# Board_power.net
KiCad netlist of a schematic drawn in Altium Designer
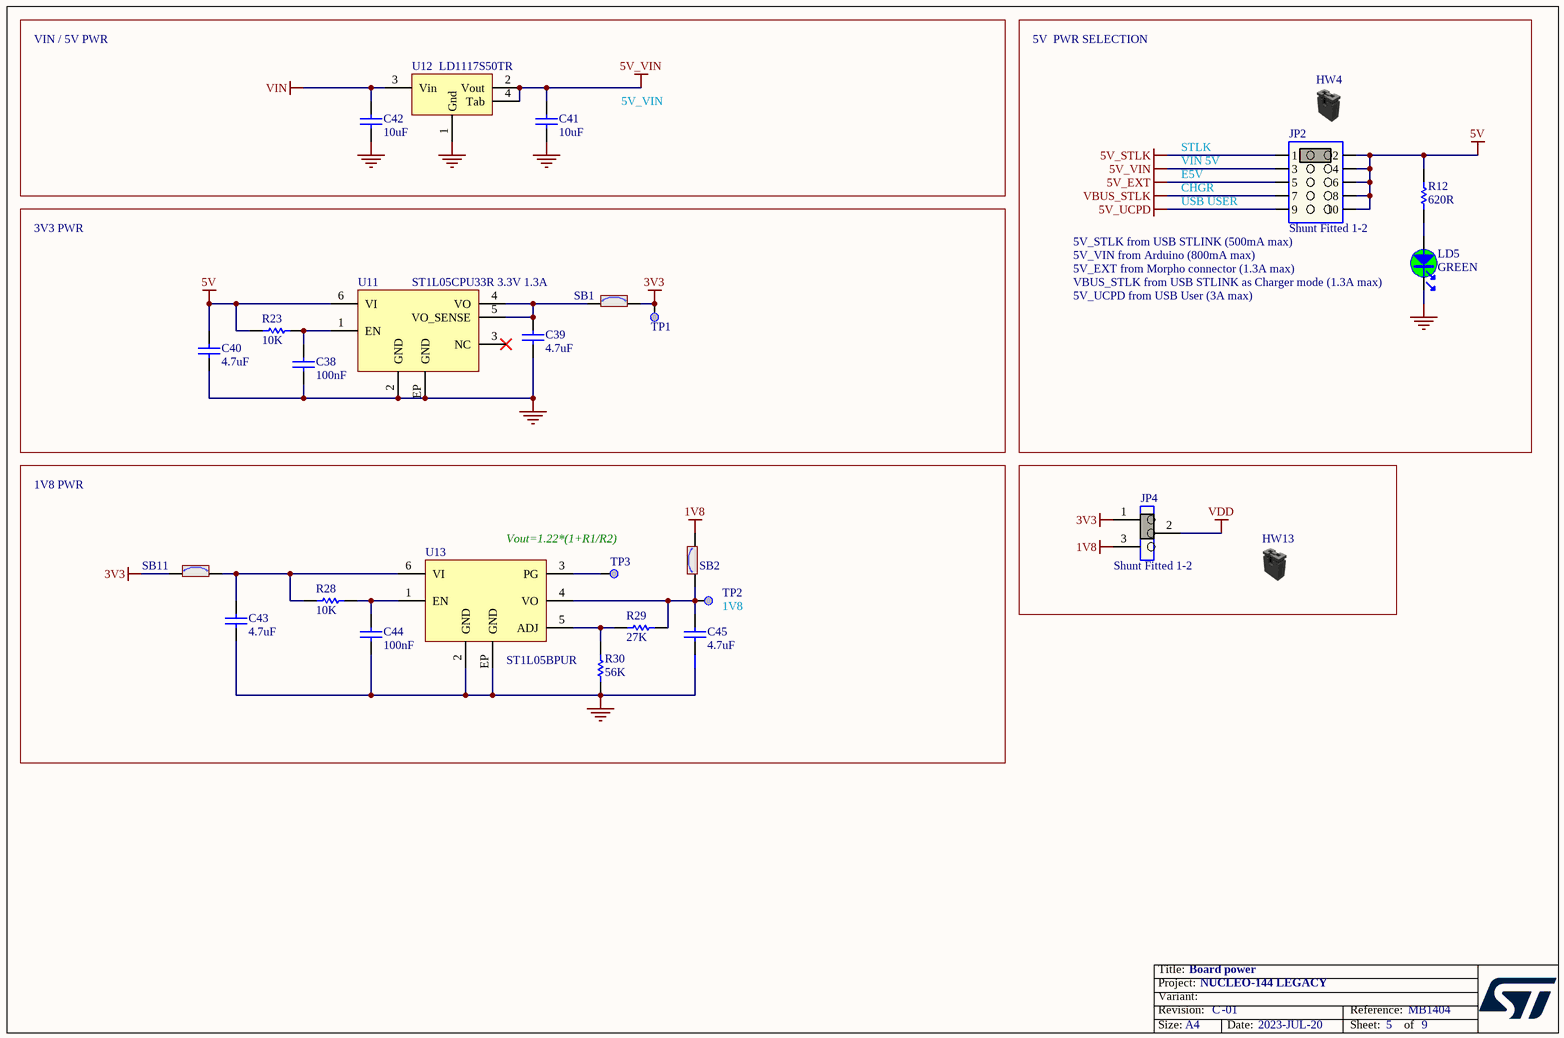
[diagram p0: Board_power.SchDoc]

(export (version "E")
  (design (tool "Eeschema 10.0.6"))
  (components
    (comp (ref "C38")
      (value "100nF")
      (footprint "MCD_PARTS:C0402")
      (description "Capacitor, MLCC, 100nF, 16V, X7R, 10%, 0402, T=0.5mm")
      (fields
        (field (name "INTERNAL_PART_NUMBER") "MCD-00006")
        (field (name "MANUFACTURER_PART_NUMBER") "CC0402KRX7R7BB104")
        (field (name "PROVIDED_BY") "SUBCO")
      )
      (libsource (lib "MCD_PARTS_database") (part "Capacitor"))
    )
    (comp (ref "C39")
      (value "4.7uF")
      (footprint "C0603_H0P8")
      (description "Capacitor, MLCC, 4.7uF, 10V, X5R, +/-20%, 0603, T=0.8mm")
      (fields (field (name "INTERNAL_PART_NUMBER") "MCD-03342") (field (name "MANUFACTURER") "YAGEO"))
      (libsource (lib "MCD_PARTS_database") (part "Capacitor"))
    )
    (comp (ref "C40")
      (value "4.7uF")
      (footprint "MCD_PARTS:C0603")
      (description "Capacitor, MLCC, 4.7uF, 16V, X5R, 20%, 0603, T=0,8mm")
      (fields
        (field (name "INTERNAL_PART_NUMBER") "MCD-00097")
        (field (name "MANUFACTURER_PART_NUMBER") "GRM188R61C475KE11")
        (field (name "PROVIDED_BY") "SUBCO")
      )
      (libsource (lib "MCD_PARTS_database") (part "Capacitor"))
    )
    (comp (ref "C41")
      (value "10uF")
      (footprint "MCD_PARTS:C0805")
      (description "Capacitor, MLCC, 10uF, 25V, X5R, 10%, 0805, T=0,85mm")
      (fields
        (field (name "INTERNAL_PART_NUMBER") "MCD-00014")
        (field (name "MANUFACTURER_PART_NUMBER") "CC0805KRX5R8BB106")
        (field (name "PROVIDED_BY") "SUBCO")
      )
      (libsource (lib "MCD_PARTS_database") (part "Capacitor"))
    )
    (comp (ref "C42")
      (value "10uF")
      (footprint "MCD_PARTS:C0805")
      (description "Capacitor, MLCC, 10uF, 25V, X5R, 10%, 0805, T=0,85mm")
      (fields
        (field (name "INTERNAL_PART_NUMBER") "MCD-00014")
        (field (name "MANUFACTURER_PART_NUMBER") "CC0805KRX5R8BB106")
        (field (name "PROVIDED_BY") "SUBCO")
      )
      (libsource (lib "MCD_PARTS_database") (part "Capacitor"))
    )
    (comp (ref "C43")
      (value "4.7uF")
      (footprint "MCD_PARTS:C0603")
      (description "Capacitor, MLCC, 4.7uF, 16V, X5R, 20%, 0603, T=0,8mm")
      (fields
        (field (name "INTERNAL_PART_NUMBER") "MCD-00097")
        (field (name "MANUFACTURER_PART_NUMBER") "GRM188R61C475KE11")
        (field (name "PROVIDED_BY") "SUBCO")
      )
      (libsource (lib "MCD_PARTS_database") (part "Capacitor"))
    )
    (comp (ref "C44")
      (value "100nF")
      (footprint "MCD_PARTS:C0402")
      (description "Capacitor, MLCC, 100nF, 16V, X7R, 10%, 0402, T=0.5mm")
      (fields
        (field (name "INTERNAL_PART_NUMBER") "MCD-00006")
        (field (name "MANUFACTURER_PART_NUMBER") "CC0402KRX7R7BB104")
        (field (name "PROVIDED_BY") "SUBCO")
      )
      (libsource (lib "MCD_PARTS_database") (part "Capacitor"))
    )
    (comp (ref "C45")
      (value "4.7uF")
      (footprint "C0603_H0P8")
      (description "Capacitor, MLCC, 4.7uF, 10V, X5R, +/-20%, 0603, T=0.8mm")
      (fields (field (name "INTERNAL_PART_NUMBER") "MCD-03342") (field (name "MANUFACTURER") "YAGEO"))
      (libsource (lib "MCD_PARTS_database") (part "Capacitor"))
    )
    (comp (ref "HW4")
      (value "Shunt Black 2.54mm")
      (description "SHUNT 2.54mm BLACK")
      (fields
        (field (name "INTERNAL_PART_NUMBER") "MCD-00043")
        (field (name "MANUFACTURER_PART_NUMBER") "SNT-100-BK-G")
        (field (name "PROVIDED_BY") "SUBCO")
      )
      (libsource (lib "MCD_PARTS_database") (part "Shunt Black 2.54mm"))
    )
    (comp (ref "HW13")
      (value "Shunt Black 2.54mm")
      (description "SHUNT 2.54mm BLACK")
      (fields
        (field (name "INTERNAL_PART_NUMBER") "MCD-00043")
        (field (name "MANUFACTURER_PART_NUMBER") "SNT-100-BK-G")
        (field (name "PROVIDED_BY") "SUBCO")
      )
      (libsource (lib "MCD_PARTS_database") (part "Shunt Black 2.54mm"))
    )
    (comp (ref "JP2")
      (value "Shunt Fitted 1-2")
      (footprint "MCD_PARTS:CON_SAMTEC_TSW-105-07-X-D")
      (description "Header, 5x2, 2,54mm, VR, TH, Height 5.84mm/2.54mm - Shunt Fitted 1-2")
      (fields (field (name "INTERNAL_PART_NUMBER") "MCD-01203") (field (name "BMS_PART_NUMBER") "9083523"))
      (libsource (lib "MCD_PARTS_database") (part "Jumper_Header 5x2 Fitted 1-2"))
    )
    (comp (ref "JP4")
      (value "Shunt Fitted 1-2")
      (footprint "MCD_PARTS:CON_SAMTEC_TSW-103-07-F-S")
      (description "Header, 3x1, 2,54mm, VR, TH, Height 5.84mm/2.54mm - Shunt Fitted 1-2 by default")
      (fields
        (field (name "INTERNAL_PART_NUMBER") "MCD-00684")
        (field (name "MANUFACTURER_PART_NUMBER") "TSW-103-07-F-S")
        (field (name "PROVIDED_BY") "SUBCO")
      )
      (libsource (lib "MCD_PARTS_database") (part "Jumper_Header 3x1 Fitted 1-2"))
    )
    (comp (ref "LD5")
      (value "GREEN")
      (footprint "MCD_PARTS:LED_0603_OSRAM_LG-Q396-PS-35_GREEN_1A2K_H0P4")
      (description "LED Green, 0603 SMD, Forward Voltage Typ=2V, Max=2.5V")
      (fields
        (field (name "INTERNAL_PART_NUMBER") "MCD-00588")
        (field (name "MANUFACTURER_PART_NUMBER") "LG Q396-PS-35")
        (field (name "PROVIDED_BY") "SUBCO")
      )
      (libsource (lib "MCD_PARTS_database") (part "LED_green"))
    )
    (comp (ref "R12")
      (value "620R")
      (footprint "MCD_PARTS:R0603")
      (description "Resistor,620R,0603,1%,1/10W")
      (fields
        (field (name "INTERNAL_PART_NUMBER") "MCD-00500")
        (field (name "MANUFACTURER_PART_NUMBER") "RC0603FR-07620RL")
        (field (name "PROVIDED_BY") "SUBCO")
      )
      (libsource (lib "MCD_PARTS_database") (part "Resistor"))
    )
    (comp (ref "R23")
      (value "10K")
      (footprint "MCD_PARTS:R0402")
      (description "Resistor,10K,0402,1%,1/16W")
      (fields
        (field (name "INTERNAL_PART_NUMBER") "MCD-00053")
        (field (name "MANUFACTURER_PART_NUMBER") "RC0402FR-0710KL")
        (field (name "PROVIDED_BY") "SUBCO")
      )
      (libsource (lib "MCD_PARTS_database") (part "Resistor"))
    )
    (comp (ref "R28")
      (value "10K")
      (footprint "MCD_PARTS:R0402")
      (description "Resistor,10K,0402,1%,1/16W")
      (fields
        (field (name "INTERNAL_PART_NUMBER") "MCD-00053")
        (field (name "MANUFACTURER_PART_NUMBER") "RC0402FR-0710KL")
        (field (name "PROVIDED_BY") "SUBCO")
      )
      (libsource (lib "MCD_PARTS_database") (part "Resistor"))
    )
    (comp (ref "R29")
      (value "27K")
      (footprint "MCD_PARTS:R0402")
      (description "Resistor,27K,0402,1%,1/16W")
      (fields
        (field (name "INTERNAL_PART_NUMBER") "MCD-00443")
        (field (name "MANUFACTURER_PART_NUMBER") "RC0402FR-0727KL")
        (field (name "PROVIDED_BY") "SUBCO")
      )
      (libsource (lib "MCD_PARTS_database") (part "Resistor"))
    )
    (comp (ref "R30")
      (value "56K")
      (footprint "MCD_PARTS:R0402")
      (description "Resistor,56K,0402,1%,1/16W")
      (fields
        (field (name "INTERNAL_PART_NUMBER") "MCD-00493")
        (field (name "MANUFACTURER_PART_NUMBER") "RC0402FR-0756KL")
        (field (name "PROVIDED_BY") "SUBCO")
      )
      (libsource (lib "MCD_PARTS_database") (part "Resistor"))
    )
    (comp (ref "SB1")
      (value "SB_ON")
      (footprint "MCD_PARTS:SOLDER-BRIDGE_R0603-0R")
      (description "Solder Bridge ON")
      (fields
        (field (name "INTERNAL_PART_NUMBER") "MCD-00071")
        (field (name "MANUFACTURER_PART_NUMBER") "RC0603JR-070RL")
        (field (name "PROVIDED_BY") "SUBCO")
      )
      (libsource (lib "MCD_PARTS_database") (part "SB_ON"))
    )
    (comp (ref "SB2")
      (value "SB_ON")
      (footprint "MCD_PARTS:SOLDER-BRIDGE_R0603-0R")
      (description "Solder Bridge ON")
      (fields
        (field (name "INTERNAL_PART_NUMBER") "MCD-00071")
        (field (name "MANUFACTURER_PART_NUMBER") "RC0603JR-070RL")
        (field (name "PROVIDED_BY") "SUBCO")
      )
      (libsource (lib "") (part "SB_ON_1"))
    )
    (comp (ref "SB11")
      (value "SB_ON")
      (footprint "MCD_PARTS:SOLDER-BRIDGE_R0603-0R")
      (description "Solder Bridge ON")
      (fields
        (field (name "INTERNAL_PART_NUMBER") "MCD-00071")
        (field (name "MANUFACTURER_PART_NUMBER") "RC0603JR-070RL")
        (field (name "PROVIDED_BY") "SUBCO")
      )
      (libsource (lib "MCD_PARTS_database") (part "SB_ON"))
    )
    (comp (ref "TP1")
      (value "Test Point")
      (footprint "MCD_PARTS:TP_SMD_1MM")
      (description "Test Point 1mm")
      (fields (field (name "INTERNAL_PART_NUMBER") "MCD-00074") (field (name "MANUFACTURER") "n/a"))
      (libsource (lib "") (part "Test Point_1"))
    )
    (comp (ref "TP2")
      (value "Test Point")
      (footprint "MCD_PARTS:TP_SMD_1MM")
      (description "Test Point 1mm")
      (fields
        (field (name "INTERNAL_PART_NUMBER") "MCD-00074")
        (field (name "MANUFACTURER_PART_NUMBER") "n/a")
      )
      (libsource (lib "MCD_PARTS_database") (part "Test Point"))
    )
    (comp (ref "TP3")
      (value "Test Point")
      (footprint "MCD_PARTS:TP_SMD_1MM")
      (description "Test Point 1mm")
      (fields
        (field (name "INTERNAL_PART_NUMBER") "MCD-00074")
        (field (name "MANUFACTURER_PART_NUMBER") "n/a")
      )
      (libsource (lib "MCD_PARTS_database") (part "Test Point"))
    )
    (comp (ref "U11")
      (value "ST1L05CPU33R 3.3V 1.3A")
      (footprint "MCD_PARTS:ICC_DFN6-EPAD_3X3_P095")
      (description "LDO, 3.3V, 1.3A, Very low quiescent current BiCMOS voltage regulator")
      (fields
        (field (name "INTERNAL_PART_NUMBER") "MCD-01025")
        (field (name "MANUFACTURER_PART_NUMBER") "ST1L05CPU33R")
        (field (name "PROVIDED_BY") "SUBCO with ST control")
      )
      (libsource (lib "MCD_PARTS_database") (part "ST1L05CPU33R"))
    )
    (comp (ref "U12")
      (value "LD1117S50TR")
      (footprint "MCD_PARTS:REG_SOT223-TAB")
      (description "IC REG LDO 5V 0.8A SOT223")
      (fields
        (field (name "INTERNAL_PART_NUMBER") "MCD-00088")
        (field (name "MANUFACTURER") "STMICROELECTRONICS")
        (field (name "PROVIDED_BY") "SUBCO with ST control")
      )
      (libsource (lib "MCD_PARTS_database") (part "LD1117S50TR"))
    )
    (comp (ref "U13")
      (value "ST1L05BPUR")
      (footprint "MCD_PARTS:ICC_DFN6-EPAD_3X3_P095")
      (description "LDO Linear Voltage Regulator IC Positive Adjustable 1 Output Adjustable 1.3A 6-DFN (3x3)")
      (fields
        (field (name "INTERNAL_PART_NUMBER") "MCD-00581")
        (field (name "MANUFACTURER") "STMICROELECTRONICS")
        (field (name "PROVIDED_BY") "SUBCO with ST control")
      )
      (libsource (lib "MCD_PARTS_database") (part "ST1L05BPUR"))
    )
  )
  (nets
    (net (code "1") (name "1V8") (class "Default")
      (node (ref "JP4") (pin "3") (pinfunction "3_3") (pintype "passive"))
      (node (ref "SB2") (pin "2") (pinfunction "2_2") (pintype "passive"))
    )
    (net (code "2") (name "3V3") (class "Default")
      (node (ref "JP4") (pin "1") (pinfunction "1_1") (pintype "passive"))
      (node (ref "SB1") (pin "2") (pinfunction "2_2") (pintype "passive"))
      (node (ref "SB11") (pin "1") (pinfunction "1_1") (pintype "passive"))
      (node (ref "TP1") (pin "1") (pinfunction "1_1") (pintype "passive"))
    )
    (net (code "3") (name "5V") (class "Default")
      (node (ref "C40") (pin "2") (pinfunction "2_2") (pintype "passive"))
      (node (ref "JP2") (pin "10") (pinfunction "10_10") (pintype "passive"))
      (node (ref "JP2") (pin "2") (pinfunction "2_2") (pintype "passive"))
      (node (ref "JP2") (pin "4") (pinfunction "4_4") (pintype "passive"))
      (node (ref "JP2") (pin "6") (pinfunction "6_6") (pintype "passive"))
      (node (ref "JP2") (pin "8") (pinfunction "8_8") (pintype "passive"))
      (node (ref "R12") (pin "2") (pinfunction "2_2") (pintype "passive"))
      (node (ref "R23") (pin "2") (pinfunction "2_2") (pintype "passive"))
      (node (ref "U11") (pin "6") (pinfunction "VI_6") (pintype "passive"))
    )
    (net (code "4") (name "5V_EXT") (class "Default")
      (node (ref "JP2") (pin "5") (pinfunction "5_5") (pintype "passive"))
    )
    (net (code "5") (name "5V_STLK") (class "Default")
      (node (ref "JP2") (pin "1") (pinfunction "1_1") (pintype "passive"))
    )
    (net (code "6") (name "5V_UCPD") (class "Default")
      (node (ref "JP2") (pin "9") (pinfunction "9_9") (pintype "passive"))
    )
    (net (code "7") (name "5V_VIN") (class "Default")
      (node (ref "C41") (pin "2") (pinfunction "2_2") (pintype "passive"))
      (node (ref "JP2") (pin "3") (pinfunction "3_3") (pintype "passive"))
      (node (ref "U12") (pin "2") (pinfunction "Vout_2") (pintype "passive"))
      (node (ref "U12") (pin "4") (pinfunction "Tab_4") (pintype "passive"))
    )
    (net (code "8") (name "GND") (class "Default")
      (node (ref "C38") (pin "2") (pinfunction "2_2") (pintype "passive"))
      (node (ref "C39") (pin "1") (pinfunction "1_1") (pintype "passive"))
      (node (ref "C40") (pin "1") (pinfunction "1_1") (pintype "passive"))
      (node (ref "C41") (pin "1") (pinfunction "1_1") (pintype "passive"))
      (node (ref "C42") (pin "1") (pinfunction "1_1") (pintype "passive"))
      (node (ref "C43") (pin "1") (pinfunction "1_1") (pintype "passive"))
      (node (ref "C44") (pin "2") (pinfunction "2_2") (pintype "passive"))
      (node (ref "C45") (pin "1") (pinfunction "1_1") (pintype "passive"))
      (node (ref "LD5") (pin "2") (pintype "passive"))
      (node (ref "R30") (pin "1") (pinfunction "1_1") (pintype "passive"))
      (node (ref "U11") (pin "2") (pinfunction "GND_2") (pintype "passive"))
      (node (ref "U11") (pin "EP") (pinfunction "GND_EP") (pintype "passive"))
      (node (ref "U12") (pin "1") (pinfunction "Gnd_1") (pintype "passive"))
      (node (ref "U13") (pin "2") (pinfunction "GND_2") (pintype "passive"))
      (node (ref "U13") (pin "EP") (pinfunction "GND_EP") (pintype "passive"))
    )
    (net (code "9") (name "Net-(LD5-Pad1)") (class "Default")
      (node (ref "LD5") (pin "1") (pintype "passive"))
      (node (ref "R12") (pin "1") (pinfunction "1_1") (pintype "passive"))
    )
    (net (code "10") (name "Net-(U11-EN)") (class "Default")
      (node (ref "C38") (pin "1") (pinfunction "1_1") (pintype "passive"))
      (node (ref "R23") (pin "1") (pinfunction "1_1") (pintype "passive"))
      (node (ref "U11") (pin "1") (pinfunction "EN_1") (pintype "passive"))
    )
    (net (code "11") (name "Net-(U11-VO)") (class "Default")
      (node (ref "C39") (pin "2") (pinfunction "2_2") (pintype "passive"))
      (node (ref "SB1") (pin "1") (pinfunction "1_1") (pintype "passive"))
      (node (ref "U11") (pin "4") (pinfunction "VO_4") (pintype "passive"))
      (node (ref "U11") (pin "5") (pinfunction "VO_SENSE_5") (pintype "passive"))
    )
    (net (code "12") (name "Net-(U13-ADJ)") (class "Default")
      (node (ref "R29") (pin "1") (pinfunction "1_1") (pintype "passive"))
      (node (ref "R30") (pin "2") (pinfunction "2_2") (pintype "passive"))
      (node (ref "U13") (pin "5") (pinfunction "ADJ_5") (pintype "passive"))
    )
    (net (code "13") (name "Net-(U13-EN)") (class "Default")
      (node (ref "C44") (pin "1") (pinfunction "1_1") (pintype "passive"))
      (node (ref "R28") (pin "1") (pinfunction "1_1") (pintype "passive"))
      (node (ref "U13") (pin "1") (pinfunction "EN_1") (pintype "passive"))
    )
    (net (code "14") (name "Net-(U13-PG)") (class "Default")
      (node (ref "TP3") (pin "1") (pinfunction "1_1") (pintype "passive"))
      (node (ref "U13") (pin "3") (pinfunction "PG_3") (pintype "passive"))
    )
    (net (code "15") (name "Net-(U13-VI)") (class "Default")
      (node (ref "C43") (pin "2") (pinfunction "2_2") (pintype "passive"))
      (node (ref "R28") (pin "2") (pinfunction "2_2") (pintype "passive"))
      (node (ref "SB11") (pin "2") (pinfunction "2_2") (pintype "passive"))
      (node (ref "U13") (pin "6") (pinfunction "VI_6") (pintype "passive"))
    )
    (net (code "16") (name "Net-(U13-VO)") (class "Default")
      (node (ref "C45") (pin "2") (pinfunction "2_2") (pintype "passive"))
      (node (ref "R29") (pin "2") (pinfunction "2_2") (pintype "passive"))
      (node (ref "SB2") (pin "1") (pinfunction "1_1") (pintype "passive"))
      (node (ref "TP2") (pin "1") (pinfunction "1_1") (pintype "passive"))
      (node (ref "U13") (pin "4") (pinfunction "VO_4") (pintype "passive"))
    )
    (net (code "17") (name "VBUS_STLK") (class "Default")
      (node (ref "JP2") (pin "7") (pinfunction "7_7") (pintype "passive"))
    )
    (net (code "18") (name "VDD") (class "Default")
      (node (ref "JP4") (pin "2") (pinfunction "2_2") (pintype "passive"))
    )
    (net (code "19") (name "VIN") (class "Default")
      (node (ref "C42") (pin "2") (pinfunction "2_2") (pintype "passive"))
      (node (ref "U12") (pin "3") (pinfunction "Vin_3") (pintype "passive"))
    )
    (net (code "20") (name "unconnected-(U11-NC-Pad3)") (class "Default")
      (node (ref "U11") (pin "3") (pinfunction "NC_3") (pintype "passive+no_connect"))
    )
  )
)
